# Power_section.net
KiCad netlist of a schematic drawn in Altium Designer
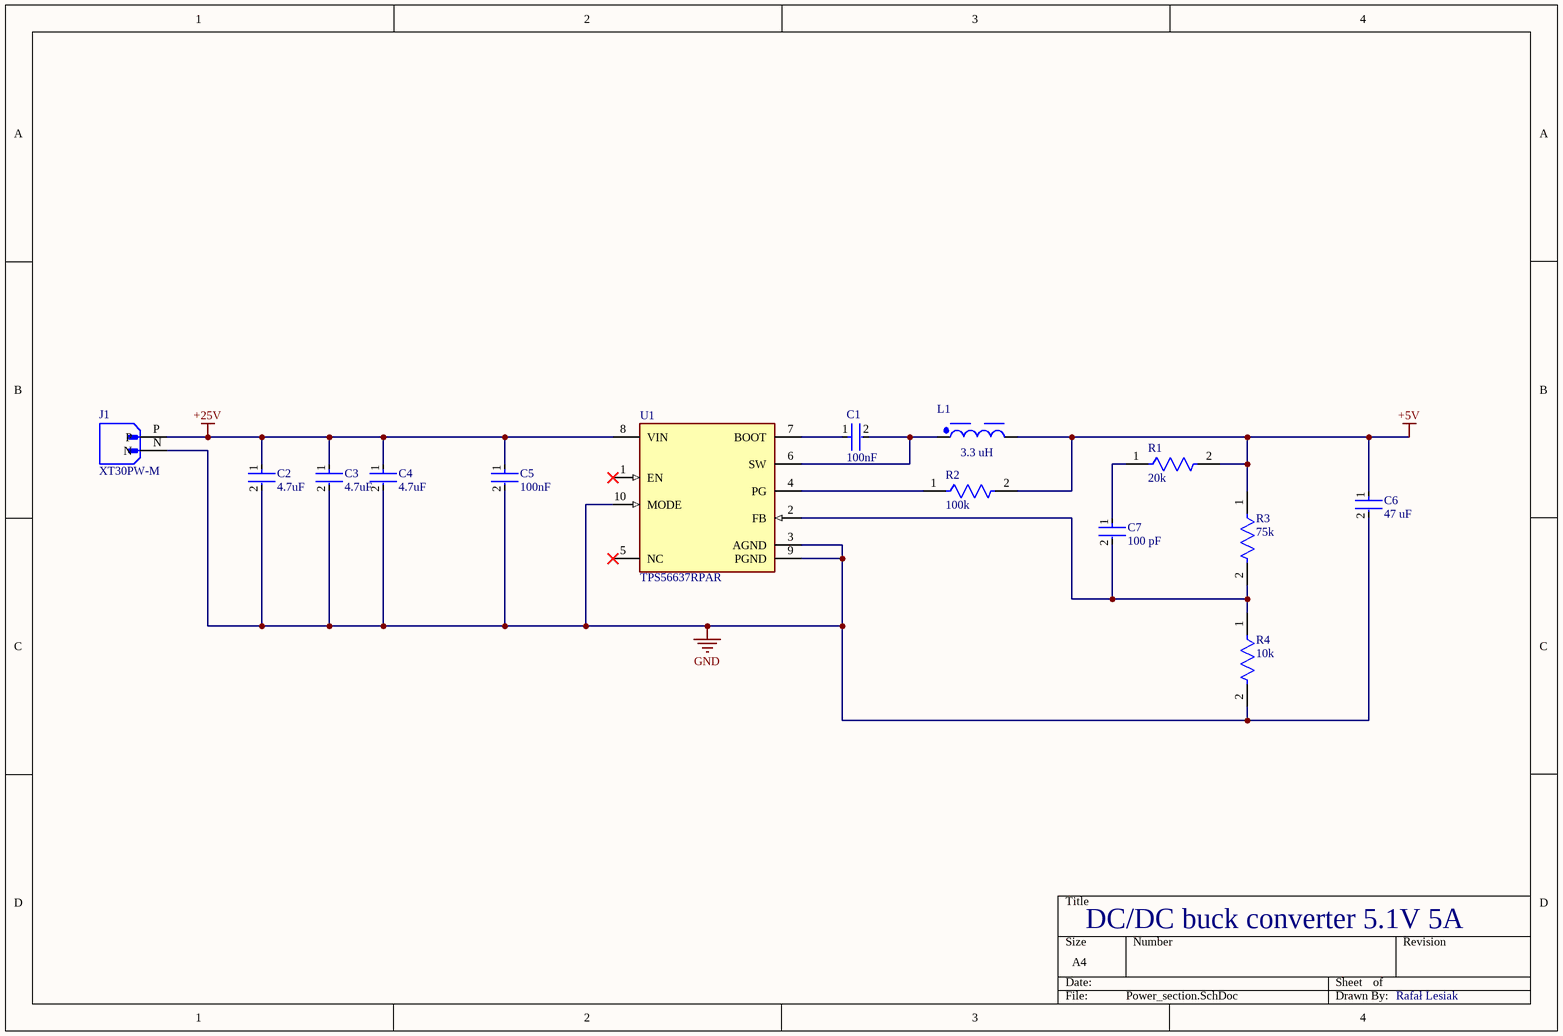
[diagram p0: Power_section.SchDoc]

(export (version "E")
  (design (tool "Eeschema 10.0.6"))
  (components
    (comp (ref "C1")
      (value "100nF")
      (footprint "FP-GRM188-0_1-e0_2_0_5-MFG")
      (description "Chip Multilayer Ceramic Capacitors for General Purpose, 0603, 0.10uF, X7R, 15%, 20%, 100V")
      (fields (field (name "TOLERANCE") "20%"))
      (libsource (lib "Altium Content Vault") (part "11868f565c42a9108669ba33697ecf6"))
    )
    (comp (ref "C2")
      (value "4.7uF")
      (footprint "FP-CC0805-0_85-MFG")
      (description "CAP CER 4.7UF 50V X5R 0805")
      (fields (field (name "TOLERANCE") "0.1") (field (name "MANUFACTURER") "Yageo"))
      (libsource (lib "Altium Content Vault") (part "11868f565c42a9108669ba33697ecf6"))
    )
    (comp (ref "C3")
      (value "4.7uF")
      (footprint "FP-CC0805-0_85-MFG")
      (description "CAP CER 4.7UF 50V X5R 0805")
      (fields (field (name "TOLERANCE") "0.1") (field (name "MANUFACTURER") "Yageo"))
      (libsource (lib "Altium Content Vault") (part "11868f565c42a9108669ba33697ecf6"))
    )
    (comp (ref "C4")
      (value "4.7uF")
      (footprint "FP-CC0805-0_85-MFG")
      (description "CAP CER 4.7UF 50V X5R 0805")
      (fields (field (name "TOLERANCE") "0.1") (field (name "MANUFACTURER") "Yageo"))
      (libsource (lib "Altium Content Vault") (part "11868f565c42a9108669ba33697ecf6"))
    )
    (comp (ref "C5")
      (value "100nF")
      (footprint "FP-GRM188-0_1-e0_2_0_5-MFG")
      (description "Chip Multilayer Ceramic Capacitors for General Purpose, 0603, 0.10uF, X7R, 15%, 20%, 100V")
      (fields (field (name "TOLERANCE") "20%"))
      (libsource (lib "Altium Content Vault") (part "11868f565c42a9108669ba33697ecf6"))
    )
    (comp (ref "C6")
      (value "47 uF")
      (footprint "FP-GRM32E-0_3-0_2-IPC_C")
      (description "CAP CER 47UF 16V X5R 1210")
      (fields (field (name "VOLTAGE") "16V") (field (name "TOLERANCE") "10%"))
      (libsource (lib "Altium Content Vault") (part "b4654b650e69147ec39a6b967a45e02"))
    )
    (comp (ref "C7")
      (value "100 pF")
      (footprint "FP-C0201-AB-MFG")
      (description "CAP CER 100PF 25V 5% NP0 0201")
      (fields
        (field (name "OCTOPART") "https://octopart.com/c0201c101k3gactu-kemet-17054818")
        (field (name "TOLERANCE") "0.1")
      )
      (libsource (lib "Altium Content Vault") (part "11868f565c42a9108669ba33697ecf6"))
    )
    (comp (ref "J1")
      (value "XT30PW-M")
      (footprint "AMASS_XT30PW-M")
      (description "Socket; DC supply; XT30; male; PIN: 2; on PCBs; THT; Colour: yellow")
      (fields (field (name "MF") "AMASS"))
      (libsource (lib "XT30PW-M") (part "XT30PW-M"))
    )
    (comp (ref "L1")
      (value "3.3 uH")
      (footprint "WE-PD_1260P")
      (description "Inductor, Aec-Q200, 3.3Uh, Shld, 9.2A Rohs Compliant: Yes")
      (fields (field (name "TOLERANCE") "30%"))
      (libsource (lib "Altium Content Vault") (part "Inductor - 2"))
    )
    (comp (ref "R1")
      (value "20k")
      (footprint "FP-AC0402-IPC_A")
      (description "RES 20kΩ ±1% 0.125W 0402")
      (libsource (lib "Altium Content Vault") (part "1029c3af85768c4190bb7ad29bc67b5"))
    )
    (comp (ref "R2")
      (value "100k")
      (footprint "FP-CRCW0402-e3-IPC_C")
      (description "RES Thick Film, 100kΩ, 1%, 0.063W, 100ppm/°C, 0402")
      (fields (field (name "TOLERANCE") "1%"))
      (libsource (lib "Altium Content Vault") (part "1029c3af85768c4190bb7ad29bc67b5"))
    )
    (comp (ref "R3")
      (value "75k")
      (footprint "FP-CR0402-IPC_C")
      (description "Thick Film Chip Resistors 0402 75kΩ 0.0625W 1% 100ppm/°C")
      (fields (field (name "TOLERANCE") "1%"))
      (libsource (lib "Altium Content Vault") (part "1029c3af85768c4190bb7ad29bc67b5"))
    )
    (comp (ref "R4")
      (value "10k")
      (footprint "FP-AC0402-IPC_C")
      (description "RES 10kΩ ±1% 0.125W 0402")
      (libsource (lib "Altium Content Vault") (part "1029c3af85768c4190bb7ad29bc67b5"))
    )
    (comp (ref "U1")
      (value "TPS56637RPAR")
      (footprint "FP-RPA0010A-MFG")
      (description "IC POWER MANAGEMENT")
      (fields
        (field (name "OCTOPART") "https://octopart.com/tps56637rpar-texas+instruments-97650653")
        (field (name "MANUFACTURER") "Texas Instruments")
      )
      (libsource (lib "Altium Content Vault") (part "31007e10bcfaaa9b7385bfd54c3e755"))
    )
  )
  (nets
    (net (code "1") (name "+5V") (class "Default")
      (node (ref "C6") (pin "1") (pinfunction "1_1") (pintype "passive"))
      (node (ref "L1") (pin "2") (pinfunction "2_2") (pintype "passive"))
      (node (ref "R1") (pin "2") (pinfunction "2_2") (pintype "passive"))
      (node (ref "R2") (pin "2") (pinfunction "2_2") (pintype "passive"))
      (node (ref "R3") (pin "1") (pinfunction "1_1") (pintype "passive"))
    )
    (net (code "2") (name "+25V") (class "Default")
      (node (ref "C2") (pin "1") (pinfunction "1_1") (pintype "passive"))
      (node (ref "C3") (pin "1") (pinfunction "1_1") (pintype "passive"))
      (node (ref "C4") (pin "1") (pinfunction "1_1") (pintype "passive"))
      (node (ref "C5") (pin "1") (pinfunction "1_1") (pintype "passive"))
      (node (ref "J1") (pin "P") (pinfunction "P_P") (pintype "power_in"))
      (node (ref "U1") (pin "8") (pinfunction "VIN_8") (pintype "power_in"))
    )
    (net (code "3") (name "GND") (class "Default")
      (node (ref "C2") (pin "2") (pinfunction "2_2") (pintype "passive"))
      (node (ref "C3") (pin "2") (pinfunction "2_2") (pintype "passive"))
      (node (ref "C4") (pin "2") (pinfunction "2_2") (pintype "passive"))
      (node (ref "C5") (pin "2") (pinfunction "2_2") (pintype "passive"))
      (node (ref "C6") (pin "2") (pinfunction "2_2") (pintype "passive"))
      (node (ref "J1") (pin "N") (pinfunction "N_N") (pintype "power_in"))
      (node (ref "R4") (pin "2") (pinfunction "2_2") (pintype "passive"))
      (node (ref "U1") (pin "10") (pinfunction "MODE_10") (pintype "input"))
      (node (ref "U1") (pin "3") (pinfunction "AGND_3") (pintype "power_in"))
      (node (ref "U1") (pin "9") (pinfunction "PGND_9") (pintype "power_in"))
    )
    (net (code "4") (name "Net-(C7-Pad1)") (class "Default")
      (node (ref "C7") (pin "1") (pinfunction "1_1") (pintype "passive"))
      (node (ref "R1") (pin "1") (pinfunction "1_1") (pintype "passive"))
    )
    (net (code "5") (name "Net-(U1-BOOT)") (class "Default")
      (node (ref "C1") (pin "1") (pinfunction "1_1") (pintype "passive"))
      (node (ref "U1") (pin "7") (pinfunction "BOOT_7") (pintype "power_in"))
    )
    (net (code "6") (name "Net-(U1-FB)") (class "Default")
      (node (ref "C7") (pin "2") (pinfunction "2_2") (pintype "passive"))
      (node (ref "R3") (pin "2") (pinfunction "2_2") (pintype "passive"))
      (node (ref "R4") (pin "1") (pinfunction "1_1") (pintype "passive"))
      (node (ref "U1") (pin "2") (pinfunction "FB_2") (pintype "input"))
    )
    (net (code "7") (name "Net-(U1-PG)") (class "Default")
      (node (ref "R2") (pin "1") (pinfunction "1_1") (pintype "passive"))
      (node (ref "U1") (pin "4") (pinfunction "PG_4") (pintype "open_collector"))
    )
    (net (code "8") (name "Net-(U1-SW)") (class "Default")
      (node (ref "C1") (pin "2") (pinfunction "2_2") (pintype "passive"))
      (node (ref "L1") (pin "1") (pinfunction "1_1") (pintype "passive"))
      (node (ref "U1") (pin "6") (pinfunction "SW_6") (pintype "power_in"))
    )
    (net (code "9") (name "unconnected-(U1-EN-Pad1)") (class "Default")
      (node (ref "U1") (pin "1") (pinfunction "EN_1") (pintype "input+no_connect"))
    )
    (net (code "10") (name "unconnected-(U1-NC-Pad5)") (class "Default")
      (node (ref "U1") (pin "5") (pinfunction "NC_5") (pintype "passive+no_connect"))
    )
  )
)
